# MainPowerCircuit.net
KiCad netlist of a schematic drawn in Altium Designer
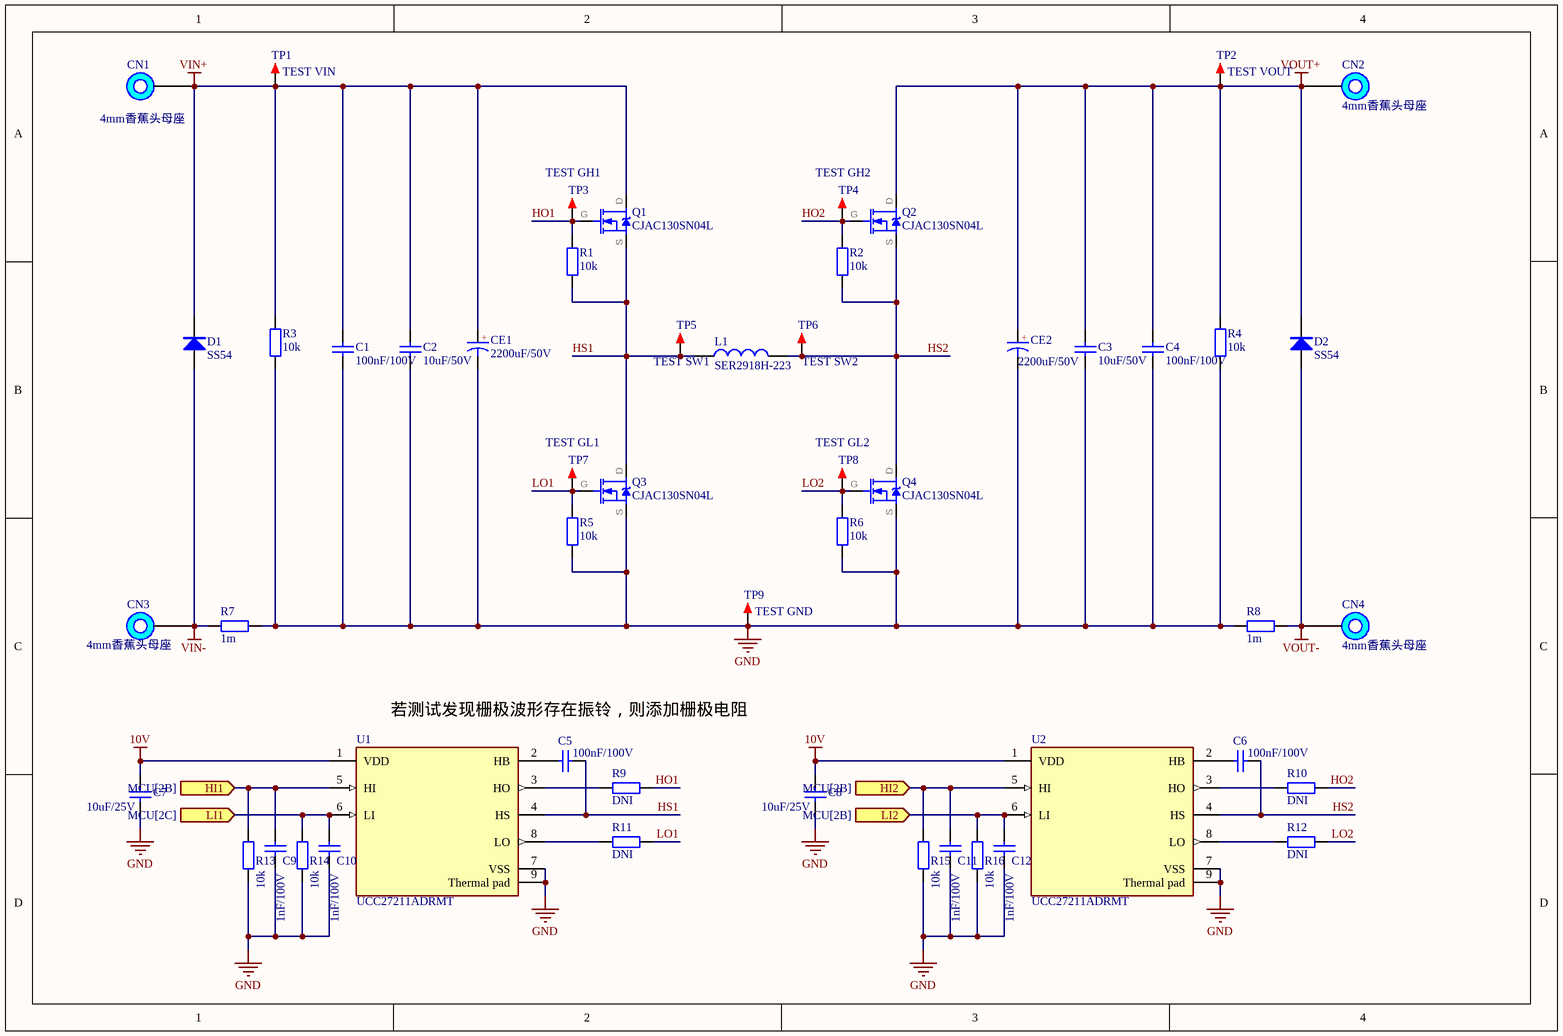
[diagram p0: MainPowerCircuit.SchDoc]

(export (version "E")
  (design (tool "Eeschema 10.0.6"))
  (components
    (comp (ref "C1")
      (value "100nF/100V")
      (footprint "C0402_L")
      (description "贴片电容")
      (libsource (lib "0.1 - 电阻-电容-电感-晶振-晶体-磁珠-电位器") (part "C"))
    )
    (comp (ref "C2")
      (value "10uF/50V")
      (footprint "C1206_L")
      (description "贴片电容")
      (libsource (lib "0.1 - 电阻-电容-电感-晶振-晶体-磁珠-电位器") (part "C"))
    )
    (comp (ref "C3")
      (value "10uF/50V")
      (footprint "C1206_L")
      (description "贴片电容")
      (libsource (lib "0.1 - 电阻-电容-电感-晶振-晶体-磁珠-电位器") (part "C"))
    )
    (comp (ref "C4")
      (value "100nF/100V")
      (footprint "C0402_L")
      (description "贴片电容")
      (libsource (lib "0.1 - 电阻-电容-电感-晶振-晶体-磁珠-电位器") (part "C"))
    )
    (comp (ref "C5")
      (value "100nF/100V")
      (footprint "C0402_L")
      (description "贴片电容")
      (libsource (lib "0.1 - 电阻-电容-电感-晶振-晶体-磁珠-电位器") (part "C"))
    )
    (comp (ref "C6")
      (value "100nF/100V")
      (footprint "C0402_L")
      (description "贴片电容")
      (libsource (lib "0.1 - 电阻-电容-电感-晶振-晶体-磁珠-电位器") (part "C"))
    )
    (comp (ref "C7")
      (value "10uF/25V")
      (footprint "C0603_L")
      (description "贴片电容")
      (libsource (lib "0.1 - 电阻-电容-电感-晶振-晶体-磁珠-电位器") (part "C"))
    )
    (comp (ref "C8")
      (value "10uF/25V")
      (footprint "C0603_L")
      (description "贴片电容")
      (libsource (lib "0.1 - 电阻-电容-电感-晶振-晶体-磁珠-电位器") (part "C"))
    )
    (comp (ref "C9")
      (value "1nF/100V")
      (footprint "C0402_L")
      (description "贴片电容")
      (libsource (lib "0.1 - 电阻-电容-电感-晶振-晶体-磁珠-电位器") (part "C"))
    )
    (comp (ref "C10")
      (value "1nF/100V")
      (footprint "C0402_L")
      (description "贴片电容")
      (libsource (lib "0.1 - 电阻-电容-电感-晶振-晶体-磁珠-电位器") (part "C"))
    )
    (comp (ref "C11")
      (value "1nF/100V")
      (footprint "C0402_L")
      (description "贴片电容")
      (libsource (lib "0.1 - 电阻-电容-电感-晶振-晶体-磁珠-电位器") (part "C"))
    )
    (comp (ref "C12")
      (value "1nF/100V")
      (footprint "C0402_L")
      (description "贴片电容")
      (libsource (lib "0.1 - 电阻-电容-电感-晶振-晶体-磁珠-电位器") (part "C"))
    )
    (comp (ref "CE1")
      (value "2200uF/50V")
      (footprint "CE-7.5*16*31.5 - GD")
      (description "直插电解电容")
      (libsource (lib "0.1 - 电阻-电容-电感-晶振-晶体-磁珠-电位器") (part "CE"))
    )
    (comp (ref "CE2")
      (value "2200uF/50V")
      (footprint "CE-7.5*16*31.5 - GD")
      (description "直插电解电容")
      (libsource (lib "0.1 - 电阻-电容-电感-晶振-晶体-磁珠-电位器") (part "CE"))
    )
    (comp (ref "CN1")
      (value "4mm香蕉头母座")
      (footprint "4mm香蕉头母座")
      (libsource (lib "DigitalBuckBoost") (part "4mm香蕉头母座"))
    )
    (comp (ref "CN2")
      (value "4mm香蕉头母座")
      (footprint "4mm香蕉头母座")
      (libsource (lib "DigitalBuckBoost") (part "4mm香蕉头母座"))
    )
    (comp (ref "CN3")
      (value "4mm香蕉头母座")
      (footprint "4mm香蕉头母座")
      (libsource (lib "DigitalBuckBoost") (part "4mm香蕉头母座"))
    )
    (comp (ref "CN4")
      (value "4mm香蕉头母座")
      (footprint "4mm香蕉头母座")
      (libsource (lib "DigitalBuckBoost") (part "4mm香蕉头母座"))
    )
    (comp (ref "D1")
      (value "SS54")
      (footprint "SMA")
      (description "肖特基二极管")
      (fields (field (name "版权归属") "源创客"))
      (libsource (lib "源创客") (part "SS14"))
    )
    (comp (ref "D2")
      (value "SS54")
      (footprint "SMA")
      (description "肖特基二极管")
      (fields (field (name "版权归属") "源创客"))
      (libsource (lib "源创客") (part "SS14"))
    )
    (comp (ref "L1")
      (value "SER2918H-223")
      (footprint "SER2918H-223")
      (description "大电流扁平线电感")
      (libsource (lib "源创客") (part "L"))
    )
    (comp (ref "Q1")
      (value "CJAC130SN04L")
      (footprint "PDFNWB5×6-8L")
      (description "130A 40V 2.0mΩ@10V N-Channel Power MOSFET")
      (libsource (lib "DigitalBuckBoost") (part "CJAC130SN04L"))
    )
    (comp (ref "Q2")
      (value "CJAC130SN04L")
      (footprint "PDFNWB5×6-8L")
      (description "130A 40V 2.0mΩ@10V N-Channel Power MOSFET")
      (libsource (lib "DigitalBuckBoost") (part "CJAC130SN04L"))
    )
    (comp (ref "Q3")
      (value "CJAC130SN04L")
      (footprint "PDFNWB5×6-8L")
      (description "130A 40V 2.0mΩ@10V N-Channel Power MOSFET")
      (libsource (lib "DigitalBuckBoost") (part "CJAC130SN04L"))
    )
    (comp (ref "Q4")
      (value "CJAC130SN04L")
      (footprint "PDFNWB5×6-8L")
      (description "130A 40V 2.0mΩ@10V N-Channel Power MOSFET")
      (libsource (lib "DigitalBuckBoost") (part "CJAC130SN04L"))
    )
    (comp (ref "R1")
      (value "10k")
      (footprint "R 0402_L")
      (description "贴片电阻")
      (fields (field (name "版权归属") "源创客"))
      (libsource (lib "源创客") (part "R"))
    )
    (comp (ref "R2")
      (value "10k")
      (footprint "R 0402_L")
      (description "贴片电阻")
      (fields (field (name "版权归属") "源创客"))
      (libsource (lib "源创客") (part "R"))
    )
    (comp (ref "R3")
      (value "10k")
      (footprint "R 0402_L")
      (description "贴片电阻")
      (fields (field (name "版权归属") "源创客"))
      (libsource (lib "源创客") (part "R"))
    )
    (comp (ref "R4")
      (value "10k")
      (footprint "R 0402_L")
      (description "贴片电阻")
      (fields (field (name "版权归属") "源创客"))
      (libsource (lib "源创客") (part "R"))
    )
    (comp (ref "R5")
      (value "10k")
      (footprint "R 0402_L")
      (description "贴片电阻")
      (fields (field (name "版权归属") "源创客"))
      (libsource (lib "源创客") (part "R"))
    )
    (comp (ref "R6")
      (value "10k")
      (footprint "R 0402_L")
      (description "贴片电阻")
      (fields (field (name "版权归属") "源创客"))
      (libsource (lib "源创客") (part "R"))
    )
    (comp (ref "R7")
      (value "1m")
      (footprint "R2512_L")
      (description "贴片电阻")
      (libsource (lib "0.1 - 电阻-电容-电感-晶振-晶体-磁珠-电位器") (part "R"))
    )
    (comp (ref "R8")
      (value "1m")
      (footprint "R2512_L")
      (description "贴片电阻")
      (libsource (lib "0.1 - 电阻-电容-电感-晶振-晶体-磁珠-电位器") (part "R"))
    )
    (comp (ref "R9")
      (value "DNI")
      (footprint "R 0402_L")
      (description "贴片电阻")
      (fields (field (name "版权归属") "源创客"))
      (libsource (lib "源创客") (part "R"))
    )
    (comp (ref "R10")
      (value "DNI")
      (footprint "R 0402_L")
      (description "贴片电阻")
      (fields (field (name "版权归属") "源创客"))
      (libsource (lib "源创客") (part "R"))
    )
    (comp (ref "R11")
      (value "DNI")
      (footprint "R 0402_L")
      (description "贴片电阻")
      (fields (field (name "版权归属") "源创客"))
      (libsource (lib "源创客") (part "R"))
    )
    (comp (ref "R12")
      (value "DNI")
      (footprint "R 0402_L")
      (description "贴片电阻")
      (fields (field (name "版权归属") "源创客"))
      (libsource (lib "源创客") (part "R"))
    )
    (comp (ref "R13")
      (value "10k")
      (footprint "R 0402_L")
      (description "贴片电阻")
      (fields (field (name "版权归属") "源创客"))
      (libsource (lib "源创客") (part "R"))
    )
    (comp (ref "R14")
      (value "10k")
      (footprint "R 0402_L")
      (description "贴片电阻")
      (fields (field (name "版权归属") "源创客"))
      (libsource (lib "源创客") (part "R"))
    )
    (comp (ref "R15")
      (value "10k")
      (footprint "R 0402_L")
      (description "贴片电阻")
      (fields (field (name "版权归属") "源创客"))
      (libsource (lib "源创客") (part "R"))
    )
    (comp (ref "R16")
      (value "10k")
      (footprint "R 0402_L")
      (description "贴片电阻")
      (fields (field (name "版权归属") "源创客"))
      (libsource (lib "源创客") (part "R"))
    )
    (comp (ref "TP1")
      (value "TEST VIN")
      (footprint "TEST TP1.4_W")
      (description "测试环")
      (libsource (lib "0.5 - 按键-开关-蜂鸣器-保险丝-电池-测试点-Mark点") (part "TEST TP"))
    )
    (comp (ref "TP2")
      (value "TEST VOUT")
      (footprint "TEST TP1.4_W")
      (description "测试环")
      (libsource (lib "0.5 - 按键-开关-蜂鸣器-保险丝-电池-测试点-Mark点") (part "TEST TP"))
    )
    (comp (ref "TP3")
      (value "TEST GH1")
      (footprint "TEST TP1.4_W")
      (description "测试环")
      (libsource (lib "0.5 - 按键-开关-蜂鸣器-保险丝-电池-测试点-Mark点") (part "TEST TP"))
    )
    (comp (ref "TP4")
      (value "TEST GH2")
      (footprint "TEST TP1.4_W")
      (description "测试环")
      (libsource (lib "0.5 - 按键-开关-蜂鸣器-保险丝-电池-测试点-Mark点") (part "TEST TP"))
    )
    (comp (ref "TP5")
      (value "TEST SW1")
      (footprint "TEST TP1.4_W")
      (description "测试环")
      (libsource (lib "0.5 - 按键-开关-蜂鸣器-保险丝-电池-测试点-Mark点") (part "TEST TP"))
    )
    (comp (ref "TP6")
      (value "TEST SW2")
      (footprint "TEST TP1.4_W")
      (description "测试环")
      (libsource (lib "0.5 - 按键-开关-蜂鸣器-保险丝-电池-测试点-Mark点") (part "TEST TP"))
    )
    (comp (ref "TP7")
      (value "TEST GL1")
      (footprint "TEST TP1.4_W")
      (description "测试环")
      (libsource (lib "0.5 - 按键-开关-蜂鸣器-保险丝-电池-测试点-Mark点") (part "TEST TP"))
    )
    (comp (ref "TP8")
      (value "TEST GL2")
      (footprint "TEST TP1.4_W")
      (description "测试环")
      (libsource (lib "0.5 - 按键-开关-蜂鸣器-保险丝-电池-测试点-Mark点") (part "TEST TP"))
    )
    (comp (ref "TP9")
      (value "TEST GND")
      (footprint "TEST TP1.4_W")
      (description "测试环")
      (libsource (lib "0.5 - 按键-开关-蜂鸣器-保险丝-电池-测试点-Mark点") (part "TEST TP"))
    )
    (comp (ref "U1")
      (value "UCC27211ADRMT")
      (footprint "FP-DRM0008A-MFG")
      (description "IC GATE DRVR HALF-BRIDGE 8VSON")
      (libsource (lib "Altium Content Vault") (part "626ca02678015058d27aa1e9fc8e5b7"))
    )
    (comp (ref "U2")
      (value "UCC27211ADRMT")
      (footprint "FP-DRM0008A-MFG")
      (description "IC GATE DRVR HALF-BRIDGE 8VSON")
      (libsource (lib "Altium Content Vault") (part "626ca02678015058d27aa1e9fc8e5b7"))
    )
  )
  (nets
    (net (code "1") (name "/HI1") (class "Default")
      (node (ref "C9") (pin "1") (pinfunction "1_1") (pintype "passive"))
      (node (ref "R13") (pin "2") (pinfunction "2_2") (pintype "passive"))
      (node (ref "U1") (pin "5") (pinfunction "HI_5") (pintype "input"))
    )
    (net (code "2") (name "/HI2") (class "Default")
      (node (ref "C11") (pin "1") (pinfunction "1_1") (pintype "passive"))
      (node (ref "R15") (pin "2") (pinfunction "2_2") (pintype "passive"))
      (node (ref "U2") (pin "5") (pinfunction "HI_5") (pintype "input"))
    )
    (net (code "3") (name "/HO1") (class "Default")
      (node (ref "Q1") (pin "G") (pinfunction "G_G") (pintype "passive"))
      (node (ref "R1") (pin "2") (pinfunction "2_2") (pintype "passive"))
      (node (ref "R9") (pin "1") (pinfunction "1_1") (pintype "passive"))
      (node (ref "TP3") (pin "1") (pinfunction "1_1") (pintype "passive"))
    )
    (net (code "4") (name "/HO2") (class "Default")
      (node (ref "Q2") (pin "G") (pinfunction "G_G") (pintype "passive"))
      (node (ref "R10") (pin "1") (pinfunction "1_1") (pintype "passive"))
      (node (ref "R2") (pin "2") (pinfunction "2_2") (pintype "passive"))
      (node (ref "TP4") (pin "1") (pinfunction "1_1") (pintype "passive"))
    )
    (net (code "5") (name "/HS1") (class "Default")
      (node (ref "C5") (pin "1") (pinfunction "1_1") (pintype "passive"))
      (node (ref "L1") (pin "1") (pinfunction "1_1") (pintype "passive"))
      (node (ref "Q1") (pin "S") (pinfunction "S_S") (pintype "passive"))
      (node (ref "Q3") (pin "D") (pinfunction "D_D") (pintype "passive"))
      (node (ref "R1") (pin "1") (pinfunction "1_1") (pintype "passive"))
      (node (ref "TP5") (pin "1") (pinfunction "1_1") (pintype "passive"))
      (node (ref "U1") (pin "4") (pinfunction "HS_4") (pintype "power_in"))
    )
    (net (code "6") (name "/HS2") (class "Default")
      (node (ref "C6") (pin "1") (pinfunction "1_1") (pintype "passive"))
      (node (ref "L1") (pin "2") (pinfunction "2_2") (pintype "passive"))
      (node (ref "Q2") (pin "S") (pinfunction "S_S") (pintype "passive"))
      (node (ref "Q4") (pin "D") (pinfunction "D_D") (pintype "passive"))
      (node (ref "R2") (pin "1") (pinfunction "1_1") (pintype "passive"))
      (node (ref "TP6") (pin "1") (pinfunction "1_1") (pintype "passive"))
      (node (ref "U2") (pin "4") (pinfunction "HS_4") (pintype "power_in"))
    )
    (net (code "7") (name "/LI1") (class "Default")
      (node (ref "C10") (pin "1") (pinfunction "1_1") (pintype "passive"))
      (node (ref "R14") (pin "2") (pinfunction "2_2") (pintype "passive"))
      (node (ref "U1") (pin "6") (pinfunction "LI_6") (pintype "input"))
    )
    (net (code "8") (name "/LI2") (class "Default")
      (node (ref "C12") (pin "1") (pinfunction "1_1") (pintype "passive"))
      (node (ref "R16") (pin "2") (pinfunction "2_2") (pintype "passive"))
      (node (ref "U2") (pin "6") (pinfunction "LI_6") (pintype "input"))
    )
    (net (code "9") (name "/LO1") (class "Default")
      (node (ref "Q3") (pin "G") (pinfunction "G_G") (pintype "passive"))
      (node (ref "R11") (pin "1") (pinfunction "1_1") (pintype "passive"))
      (node (ref "R5") (pin "2") (pinfunction "2_2") (pintype "passive"))
      (node (ref "TP7") (pin "1") (pinfunction "1_1") (pintype "passive"))
    )
    (net (code "10") (name "/LO2") (class "Default")
      (node (ref "Q4") (pin "G") (pinfunction "G_G") (pintype "passive"))
      (node (ref "R12") (pin "1") (pinfunction "1_1") (pintype "passive"))
      (node (ref "R6") (pin "2") (pinfunction "2_2") (pintype "passive"))
      (node (ref "TP8") (pin "1") (pinfunction "1_1") (pintype "passive"))
    )
    (net (code "11") (name "10V") (class "Default")
      (node (ref "C7") (pin "2") (pinfunction "2_2") (pintype "passive"))
      (node (ref "C8") (pin "2") (pinfunction "2_2") (pintype "passive"))
      (node (ref "U1") (pin "1") (pinfunction "VDD_1") (pintype "power_in"))
      (node (ref "U2") (pin "1") (pinfunction "VDD_1") (pintype "power_in"))
    )
    (net (code "12") (name "GND") (class "Default")
      (node (ref "C1") (pin "1") (pinfunction "1_1") (pintype "passive"))
      (node (ref "C10") (pin "2") (pinfunction "2_2") (pintype "passive"))
      (node (ref "C11") (pin "2") (pinfunction "2_2") (pintype "passive"))
      (node (ref "C12") (pin "2") (pinfunction "2_2") (pintype "passive"))
      (node (ref "C2") (pin "1") (pinfunction "1_1") (pintype "passive"))
      (node (ref "C3") (pin "1") (pinfunction "1_1") (pintype "passive"))
      (node (ref "C4") (pin "1") (pinfunction "1_1") (pintype "passive"))
      (node (ref "C7") (pin "1") (pinfunction "1_1") (pintype "passive"))
      (node (ref "C8") (pin "1") (pinfunction "1_1") (pintype "passive"))
      (node (ref "C9") (pin "2") (pinfunction "2_2") (pintype "passive"))
      (node (ref "CE1") (pin "2") (pinfunction "2_2") (pintype "passive"))
      (node (ref "CE2") (pin "2") (pinfunction "2_2") (pintype "passive"))
      (node (ref "Q3") (pin "S") (pinfunction "S_S") (pintype "passive"))
      (node (ref "Q4") (pin "S") (pinfunction "S_S") (pintype "passive"))
      (node (ref "R13") (pin "1") (pinfunction "1_1") (pintype "passive"))
      (node (ref "R14") (pin "1") (pinfunction "1_1") (pintype "passive"))
      (node (ref "R15") (pin "1") (pinfunction "1_1") (pintype "passive"))
      (node (ref "R16") (pin "1") (pinfunction "1_1") (pintype "passive"))
      (node (ref "R3") (pin "1") (pinfunction "1_1") (pintype "passive"))
      (node (ref "R4") (pin "1") (pinfunction "1_1") (pintype "passive"))
      (node (ref "R5") (pin "1") (pinfunction "1_1") (pintype "passive"))
      (node (ref "R6") (pin "1") (pinfunction "1_1") (pintype "passive"))
      (node (ref "R7") (pin "2") (pinfunction "2_2") (pintype "passive"))
      (node (ref "R8") (pin "1") (pinfunction "1_1") (pintype "passive"))
      (node (ref "TP9") (pin "1") (pinfunction "1_1") (pintype "passive"))
      (node (ref "U1") (pin "7") (pinfunction "VSS_7") (pintype "power_in"))
      (node (ref "U1") (pin "9") (pinfunction "Thermal_pad_9") (pintype "power_in"))
      (node (ref "U2") (pin "7") (pinfunction "VSS_7") (pintype "power_in"))
      (node (ref "U2") (pin "9") (pinfunction "Thermal_pad_9") (pintype "power_in"))
    )
    (net (code "13") (name "Net-(U1-HB)") (class "Default")
      (node (ref "C5") (pin "2") (pinfunction "2_2") (pintype "passive"))
      (node (ref "U1") (pin "2") (pinfunction "HB_2") (pintype "power_in"))
    )
    (net (code "14") (name "Net-(U1-HO)") (class "Default")
      (node (ref "R9") (pin "2") (pinfunction "2_2") (pintype "passive"))
      (node (ref "U1") (pin "3") (pinfunction "HO_3") (pintype "output"))
    )
    (net (code "15") (name "Net-(U1-LO)") (class "Default")
      (node (ref "R11") (pin "2") (pinfunction "2_2") (pintype "passive"))
      (node (ref "U1") (pin "8") (pinfunction "LO_8") (pintype "output"))
    )
    (net (code "16") (name "Net-(U2-HB)") (class "Default")
      (node (ref "C6") (pin "2") (pinfunction "2_2") (pintype "passive"))
      (node (ref "U2") (pin "2") (pinfunction "HB_2") (pintype "power_in"))
    )
    (net (code "17") (name "Net-(U2-HO)") (class "Default")
      (node (ref "R10") (pin "2") (pinfunction "2_2") (pintype "passive"))
      (node (ref "U2") (pin "3") (pinfunction "HO_3") (pintype "output"))
    )
    (net (code "18") (name "Net-(U2-LO)") (class "Default")
      (node (ref "R12") (pin "2") (pinfunction "2_2") (pintype "passive"))
      (node (ref "U2") (pin "8") (pinfunction "LO_8") (pintype "output"))
    )
    (net (code "19") (name "VIN+") (class "Default")
      (node (ref "C1") (pin "2") (pinfunction "2_2") (pintype "passive"))
      (node (ref "C2") (pin "2") (pinfunction "2_2") (pintype "passive"))
      (node (ref "CE1") (pin "1") (pinfunction "1_1") (pintype "passive"))
      (node (ref "CN1") (pin "1") (pintype "passive"))
      (node (ref "D1") (pin "2") (pinfunction "K_2") (pintype "passive"))
      (node (ref "Q1") (pin "D") (pinfunction "D_D") (pintype "passive"))
      (node (ref "R3") (pin "2") (pinfunction "2_2") (pintype "passive"))
      (node (ref "TP1") (pin "1") (pinfunction "1_1") (pintype "passive"))
    )
    (net (code "20") (name "VIN-") (class "Default")
      (node (ref "CN3") (pin "1") (pintype "passive"))
      (node (ref "D1") (pin "1") (pinfunction "A_1") (pintype "passive"))
      (node (ref "R7") (pin "1") (pinfunction "1_1") (pintype "passive"))
    )
    (net (code "21") (name "VOUT+") (class "Default")
      (node (ref "C3") (pin "2") (pinfunction "2_2") (pintype "passive"))
      (node (ref "C4") (pin "2") (pinfunction "2_2") (pintype "passive"))
      (node (ref "CE2") (pin "1") (pinfunction "1_1") (pintype "passive"))
      (node (ref "CN2") (pin "1") (pintype "passive"))
      (node (ref "D2") (pin "2") (pinfunction "K_2") (pintype "passive"))
      (node (ref "Q2") (pin "D") (pinfunction "D_D") (pintype "passive"))
      (node (ref "R4") (pin "2") (pinfunction "2_2") (pintype "passive"))
      (node (ref "TP2") (pin "1") (pinfunction "1_1") (pintype "passive"))
    )
    (net (code "22") (name "VOUT-") (class "Default")
      (node (ref "CN4") (pin "1") (pintype "passive"))
      (node (ref "D2") (pin "1") (pinfunction "A_1") (pintype "passive"))
      (node (ref "R8") (pin "2") (pinfunction "2_2") (pintype "passive"))
    )
  )
)
